# photo-relay.net
KiCad netlist of a schematic drawn in EAGLE
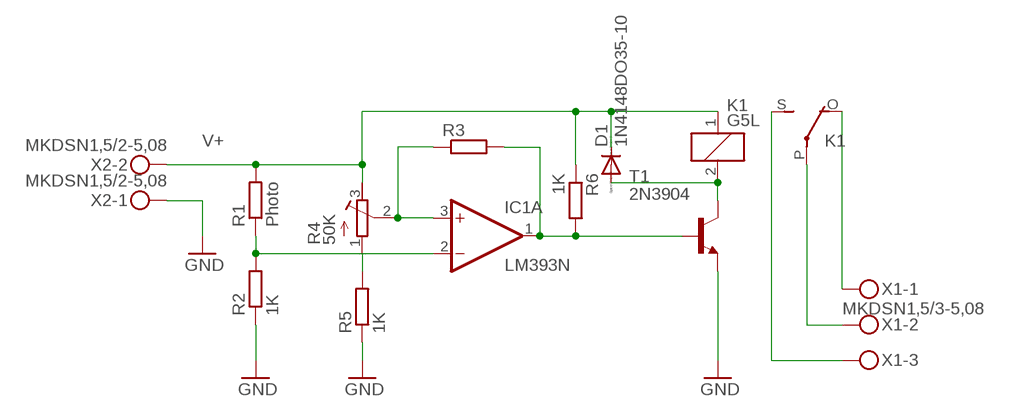
[diagram p0: schematic, sheet 1]

(export (version "E")
  (design (tool "Eeschema 10.0.6"))
  (components
    (comp (ref "D1")
      (value "1N4148DO35-10")
      (footprint "eagle-import:DO35-10")
      (libsource (lib "eagle-import") (part "1N4148DO35-10"))
    )
    (comp (ref "IC1")
      (value "LM393N")
      (footprint "eagle-import:DIL08")
      (libsource (lib "eagle-import") (part "LM393N"))
    )
    (comp (ref "K1")
      (value "G5L")
      (footprint "eagle-import:G5LE")
      (libsource (lib "eagle-import") (part "G5L"))
    )
    (comp (ref "R1")
      (value "Photo")
      (footprint "eagle-import:0204_7")
      (libsource (lib "eagle-import") (part "R-EU_0204/7"))
    )
    (comp (ref "R2")
      (value "1K")
      (footprint "eagle-import:0204_7")
      (libsource (lib "eagle-import") (part "R-EU_0204/7"))
    )
    (comp (ref "R3")
      (value "R-EU_0204/7")
      (footprint "eagle-import:0204_7")
      (libsource (lib "eagle-import") (part "R-EU_0204/7"))
    )
    (comp (ref "R4")
      (value "50K")
      (footprint "eagle-import:RTRIM64W")
      (libsource (lib "eagle-import") (part "R-TRIMM64W"))
    )
    (comp (ref "R5")
      (value "1K")
      (footprint "eagle-import:0204_7")
      (libsource (lib "eagle-import") (part "R-EU_0204/7"))
    )
    (comp (ref "R6")
      (value "1K")
      (footprint "eagle-import:0204_7")
      (libsource (lib "eagle-import") (part "R-EU_0204/7"))
    )
    (comp (ref "T1")
      (value "2N3904")
      (footprint "eagle-import:TO92")
      (libsource (lib "eagle-import") (part "2N3904"))
    )
    (comp (ref "X1")
      (value "MKDSN1,5/3-5,08")
      (footprint "eagle-import:MKDSN1,5_3-5,08")
      (libsource (lib "eagle-import") (part "MKDSN1,5/3-5,08"))
    )
    (comp (ref "X2")
      (value "MKDSN1,5/2-5,08")
      (footprint "eagle-import:MKDSN1,5_2-5,08")
      (libsource (lib "eagle-import") (part "MKDSN1,5/2-5,08"))
    )
  )
  (nets
    (net (code "1") (name "/V+") (class "Default")
      (node (ref "D1") (pin "C") (pinfunction "C_C") (pintype "passive"))
      (node (ref "K1") (pin "1") (pinfunction "1_1") (pintype "passive"))
      (node (ref "R1") (pin "2") (pinfunction "2_2") (pintype "passive"))
      (node (ref "R4") (pin "3") (pinfunction "E_3") (pintype "passive"))
      (node (ref "R6") (pin "1") (pinfunction "1_1") (pintype "passive"))
      (node (ref "X2") (pin "2") (pinfunction "KL_2") (pintype "passive"))
    )
    (net (code "2") (name "GND") (class "Default")
      (node (ref "R2") (pin "1") (pinfunction "1_1") (pintype "passive"))
      (node (ref "R5") (pin "1") (pinfunction "1_1") (pintype "passive"))
      (node (ref "T1") (pin "3") (pinfunction "E_3") (pintype "passive"))
      (node (ref "X2") (pin "1") (pinfunction "KL_1") (pintype "passive"))
    )
    (net (code "3") (name "Net-(IC1A-+IN)") (class "Default")
      (node (ref "IC1") (pin "3") (pinfunction "+IN_3") (pintype "input"))
      (node (ref "R3") (pin "1") (pinfunction "1_1") (pintype "passive"))
      (node (ref "R4") (pin "2") (pinfunction "S_2") (pintype "passive"))
    )
    (net (code "4") (name "Net-(IC1A--IN)") (class "Default")
      (node (ref "IC1") (pin "2") (pinfunction "-IN_2") (pintype "input"))
      (node (ref "R1") (pin "1") (pinfunction "1_1") (pintype "passive"))
      (node (ref "R2") (pin "2") (pinfunction "2_2") (pintype "passive"))
    )
    (net (code "5") (name "Net-(IC1A-OUT)") (class "Default")
      (node (ref "IC1") (pin "1") (pinfunction "OUT_1") (pintype "output"))
      (node (ref "R3") (pin "2") (pinfunction "2_2") (pintype "passive"))
      (node (ref "R6") (pin "2") (pinfunction "2_2") (pintype "passive"))
      (node (ref "T1") (pin "2") (pinfunction "B_2") (pintype "passive"))
    )
    (net (code "6") (name "Net-(R4-A)") (class "Default")
      (node (ref "R4") (pin "1") (pinfunction "A_1") (pintype "passive"))
      (node (ref "R5") (pin "2") (pinfunction "2_2") (pintype "passive"))
    )
    (net (code "7") (name "Net-(T1-C)") (class "Default")
      (node (ref "D1") (pin "A") (pinfunction "A_A") (pintype "passive"))
      (node (ref "K1") (pin "2") (pinfunction "2_2") (pintype "passive"))
      (node (ref "T1") (pin "1") (pinfunction "C_1") (pintype "passive"))
    )
    (net (code "8") (name "Net-(X1A-KL)") (class "Default")
      (node (ref "K1") (pin "O") (pinfunction "O_O") (pintype "passive"))
      (node (ref "X1") (pin "1") (pinfunction "KL_1") (pintype "passive"))
    )
    (net (code "9") (name "Net-(X1B-KL)") (class "Default")
      (node (ref "K1") (pin "P") (pinfunction "P_P") (pintype "passive"))
      (node (ref "X1") (pin "2") (pinfunction "KL_2") (pintype "passive"))
    )
    (net (code "10") (name "Net-(X1C-KL)") (class "Default")
      (node (ref "K1") (pin "S") (pinfunction "S_S") (pintype "passive"))
      (node (ref "X1") (pin "3") (pinfunction "KL_3") (pintype "passive"))
    )
  )
)
